# imu_69-v2.net
KiCad netlist of a schematic drawn in EAGLE
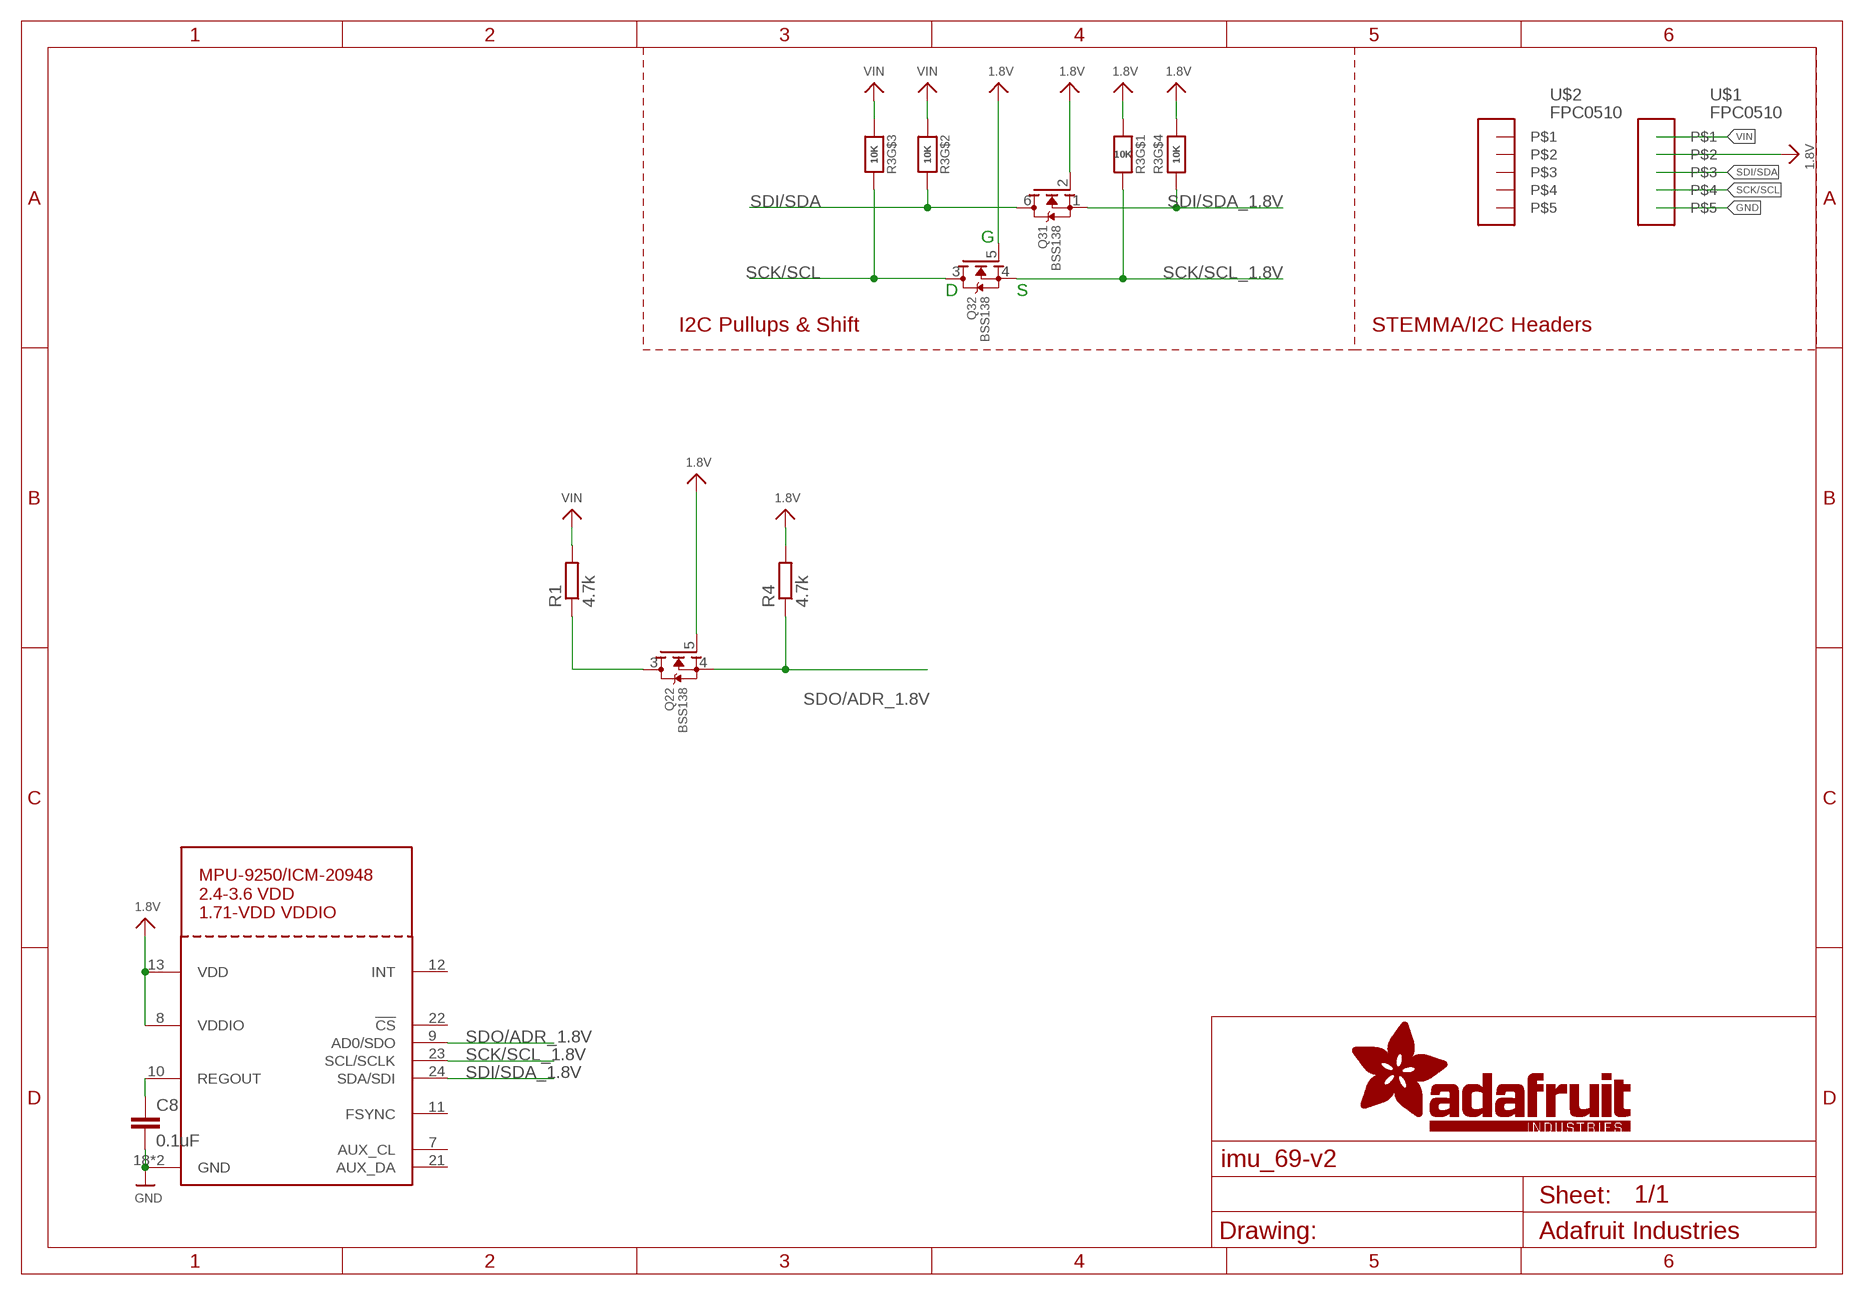
[diagram p0: schematic, sheet 1]

(export (version "E")
  (design (tool "Eeschema 10.0.6"))
  (components
    (comp (ref "C8")
      (value "0.1uF")
      (footprint "eagle-import:C0201")
      (libsource (lib "eagle-import") (part "C-EUC0201"))
    )
    (comp (ref "Q2")
      (value "BSS138")
      (footprint "eagle-import:SOT363")
      (libsource (lib "eagle-import") (part "MOSFET-N_DUAL"))
    )
    (comp (ref "Q3")
      (value "BSS138")
      (footprint "eagle-import:SOT363")
      (libsource (lib "eagle-import") (part "MOSFET-N_DUAL"))
    )
    (comp (ref "R1")
      (value "4.7k")
      (footprint "eagle-import:R0402")
      (libsource (lib "eagle-import") (part "R-EU_R0402"))
    )
    (comp (ref "R3")
      (value "10K")
      (footprint "eagle-import:RESPACK_4X0603")
      (libsource (lib "eagle-import") (part "RESISTOR_4PACK"))
    )
    (comp (ref "R4")
      (value "4.7k")
      (footprint "eagle-import:R0402")
      (libsource (lib "eagle-import") (part "R-EU_R0402"))
    )
    (comp (ref "U$1")
      (value "FPC0510")
      (footprint "eagle-import:FPC0510")
      (libsource (lib "eagle-import") (part "FPC0510"))
    )
    (comp (ref "U$2")
      (value "FPC0510")
      (footprint "eagle-import:FPC0510")
      (libsource (lib "eagle-import") (part "FPC0510"))
    )
    (comp (ref "U$21")
      (value "MPU-9250_ICM20948")
      (footprint "eagle-import:QFN24_3MM_NOEP")
      (libsource (lib "eagle-import") (part "MPU-9250_ICM20948"))
    )
  )
  (nets
    (net (code "1") (name "/SCK{slash}SCL_1.8V") (class "Default")
      (node (ref "Q3") (pin "4") (pinfunction "S_4") (pintype "bidirectional"))
      (node (ref "R3") (pin "1") (pinfunction "1_1") (pintype "passive"))
      (node (ref "U$21") (pin "23") (pinfunction "SCL/SCLK_23") (pintype "bidirectional"))
    )
    (net (code "2") (name "/SDI{slash}SDA_1.8V") (class "Default")
      (node (ref "Q3") (pin "1") (pinfunction "S_1") (pintype "bidirectional"))
      (node (ref "R3") (pin "5") (pinfunction "2_5") (pintype "passive"))
      (node (ref "U$21") (pin "24") (pinfunction "SDA/SDI_24") (pintype "bidirectional"))
    )
    (net (code "3") (name "/SDO{slash}ADR_1.8V") (class "Default")
      (node (ref "Q2") (pin "4") (pinfunction "S_4") (pintype "bidirectional"))
      (node (ref "R4") (pin "1") (pinfunction "1_1") (pintype "passive"))
      (node (ref "U$21") (pin "9") (pinfunction "AD0/SDO_9") (pintype "bidirectional"))
    )
    (net (code "4") (name "1.8V") (class "Default")
      (node (ref "Q2") (pin "5") (pinfunction "G_5") (pintype "bidirectional"))
      (node (ref "Q3") (pin "2") (pinfunction "G_2") (pintype "bidirectional"))
      (node (ref "Q3") (pin "5") (pinfunction "G_5") (pintype "bidirectional"))
      (node (ref "R3") (pin "4") (pinfunction "1_4") (pintype "passive"))
      (node (ref "R3") (pin "8") (pinfunction "2_8") (pintype "passive"))
      (node (ref "R4") (pin "2") (pinfunction "2_2") (pintype "passive"))
      (node (ref "U$1") (pin "P$2") (pinfunction "P$2_P$2") (pintype "bidirectional"))
      (node (ref "U$21") (pin "13") (pinfunction "VDD_13") (pintype "bidirectional"))
      (node (ref "U$21") (pin "8") (pinfunction "VDDIO_8") (pintype "bidirectional"))
    )
    (net (code "5") (name "GND") (class "Default")
      (node (ref "C8") (pin "2") (pinfunction "2_2") (pintype "passive"))
      (node (ref "U$1") (pin "P$5") (pinfunction "P$5_P$5") (pintype "bidirectional"))
      (node (ref "U$21") (pin "18") (pinfunction "GND_18") (pintype "bidirectional"))
      (node (ref "U$21") (pin "20") (pinfunction "GND_20") (pintype "bidirectional"))
    )
    (net (code "6") (name "Net-(Q2B-D)") (class "Default")
      (node (ref "Q2") (pin "3") (pinfunction "D_3") (pintype "bidirectional"))
      (node (ref "R1") (pin "1") (pinfunction "1_1") (pintype "passive"))
    )
    (net (code "7") (name "Net-(U$21-REGOUT)") (class "Default")
      (node (ref "C8") (pin "1") (pinfunction "1_1") (pintype "passive"))
      (node (ref "U$21") (pin "10") (pinfunction "REGOUT_10") (pintype "bidirectional"))
    )
    (net (code "8") (name "SCK{slash}SCL") (class "Default")
      (node (ref "Q3") (pin "3") (pinfunction "D_3") (pintype "bidirectional"))
      (node (ref "R3") (pin "6") (pinfunction "2_6") (pintype "passive"))
      (node (ref "U$1") (pin "P$4") (pinfunction "P$4_P$4") (pintype "bidirectional"))
    )
    (net (code "9") (name "SDI{slash}SDA") (class "Default")
      (node (ref "Q3") (pin "6") (pinfunction "D_6") (pintype "bidirectional"))
      (node (ref "R3") (pin "7") (pinfunction "2_7") (pintype "passive"))
      (node (ref "U$1") (pin "P$3") (pinfunction "P$3_P$3") (pintype "bidirectional"))
    )
    (net (code "10") (name "VIN") (class "Default")
      (node (ref "R1") (pin "2") (pinfunction "2_2") (pintype "passive"))
      (node (ref "R3") (pin "2") (pinfunction "1_2") (pintype "passive"))
      (node (ref "R3") (pin "3") (pinfunction "1_3") (pintype "passive"))
      (node (ref "U$1") (pin "P$1") (pinfunction "P$1_P$1") (pintype "bidirectional"))
    )
    (net (code "11") (name "unconnected-(U$2-PadP$1)") (class "Default")
      (node (ref "U$2") (pin "P$1") (pinfunction "P$1_P$1") (pintype "bidirectional"))
    )
    (net (code "12") (name "unconnected-(U$2-PadP$2)") (class "Default")
      (node (ref "U$2") (pin "P$2") (pinfunction "P$2_P$2") (pintype "bidirectional"))
    )
    (net (code "13") (name "unconnected-(U$2-PadP$3)") (class "Default")
      (node (ref "U$2") (pin "P$3") (pinfunction "P$3_P$3") (pintype "bidirectional"))
    )
    (net (code "14") (name "unconnected-(U$2-PadP$4)") (class "Default")
      (node (ref "U$2") (pin "P$4") (pinfunction "P$4_P$4") (pintype "bidirectional"))
    )
    (net (code "15") (name "unconnected-(U$2-PadP$5)") (class "Default")
      (node (ref "U$2") (pin "P$5") (pinfunction "P$5_P$5") (pintype "bidirectional"))
    )
    (net (code "16") (name "unconnected-(U$21-AUX_CL-Pad7)") (class "Default")
      (node (ref "U$21") (pin "7") (pinfunction "AUX_CL_7") (pintype "bidirectional"))
    )
    (net (code "17") (name "unconnected-(U$21-AUX_DA-Pad21)") (class "Default")
      (node (ref "U$21") (pin "21") (pinfunction "AUX_DA_21") (pintype "bidirectional"))
    )
    (net (code "18") (name "unconnected-(U$21-FSYNC-Pad11)") (class "Default")
      (node (ref "U$21") (pin "11") (pinfunction "FSYNC_11") (pintype "bidirectional"))
    )
    (net (code "19") (name "unconnected-(U$21-INT-Pad12)") (class "Default")
      (node (ref "U$21") (pin "12") (pinfunction "INT_12") (pintype "bidirectional"))
    )
    (net (code "20") (name "unconnected-(U$21-~{CS}-Pad22)") (class "Default")
      (node (ref "U$21") (pin "22") (pinfunction "~{CS}_22") (pintype "bidirectional"))
    )
  )
)
